# dmf.net
KiCad netlist of a schematic drawn in EAGLE
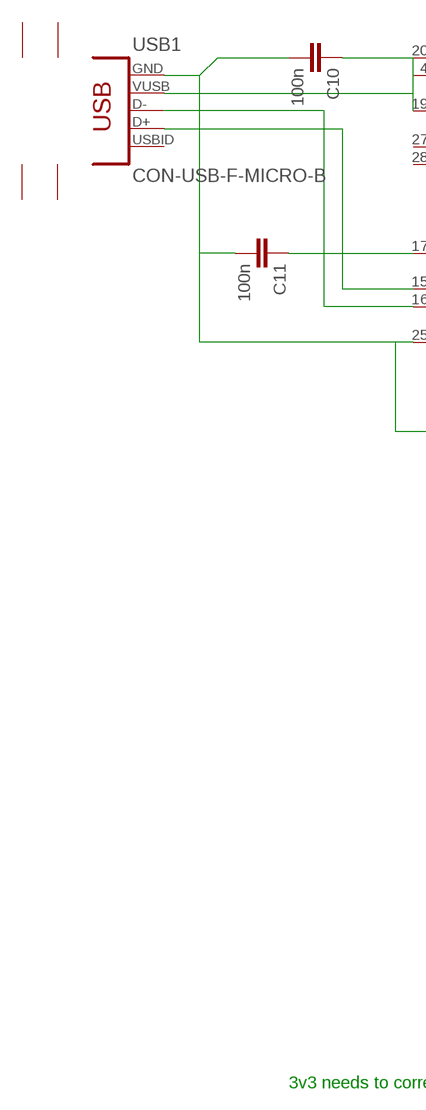
[diagram p0: schematic, sheet 1, part 1 of 2]
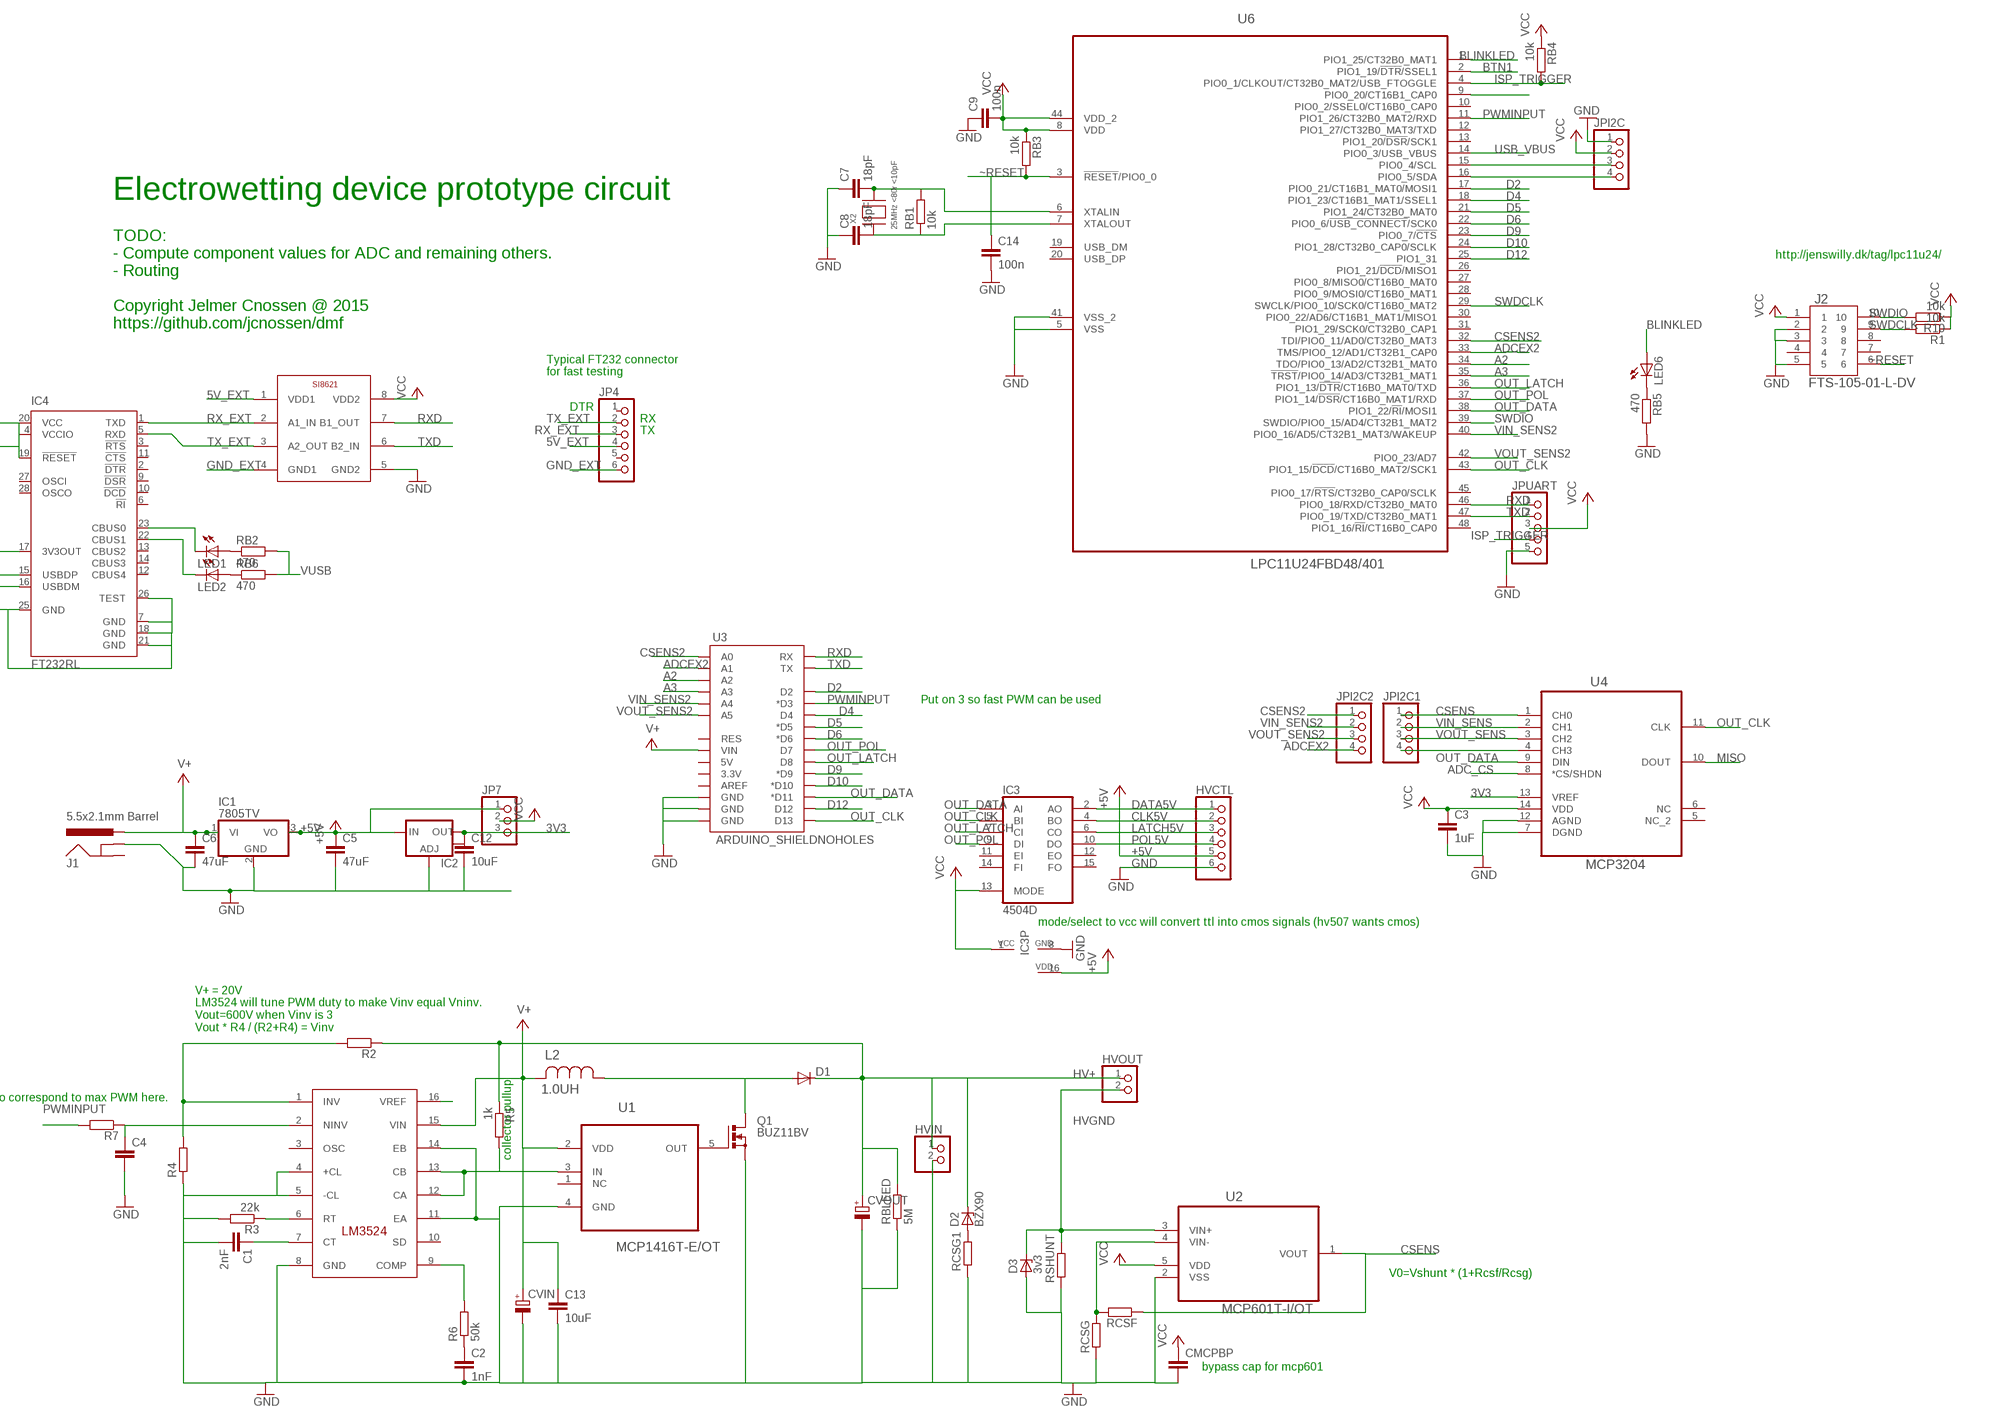
[diagram p1: schematic, sheet 1, part 2 of 2]

(export (version "E")
  (design (tool "Eeschema 10.0.6"))
  (components
    (comp (ref "C1")
      (value "2nF")
      (footprint "eagle-import:C0805")
      (libsource (lib "eagle-import") (part "C-EUC0805"))
    )
    (comp (ref "C2")
      (value "1nF")
      (footprint "eagle-import:C0805")
      (libsource (lib "eagle-import") (part "C-EUC0805"))
    )
    (comp (ref "C3")
      (value "1uF")
      (footprint "eagle-import:C0805")
      (libsource (lib "eagle-import") (part "C-EUC0805"))
    )
    (comp (ref "C4")
      (value "C-EUC0805")
      (footprint "eagle-import:C0805")
      (libsource (lib "eagle-import") (part "C-EUC0805"))
    )
    (comp (ref "C5")
      (value "47uF")
      (footprint "eagle-import:C1206")
      (libsource (lib "eagle-import") (part "C-EUC1206"))
    )
    (comp (ref "C6")
      (value "47uF")
      (footprint "eagle-import:C1206")
      (libsource (lib "eagle-import") (part "C-EUC1206"))
    )
    (comp (ref "C7")
      (value "18pF")
      (footprint "eagle-import:C0805")
      (libsource (lib "eagle-import") (part "C-EUC0805"))
    )
    (comp (ref "C8")
      (value "18pF")
      (footprint "eagle-import:C0805")
      (libsource (lib "eagle-import") (part "C-EUC0805"))
    )
    (comp (ref "C9")
      (value "100n")
      (footprint "eagle-import:C0805")
      (libsource (lib "eagle-import") (part "C-EUC0805"))
    )
    (comp (ref "C10")
      (value "100n")
      (footprint "eagle-import:C0805")
      (libsource (lib "eagle-import") (part "C-EUC0805"))
    )
    (comp (ref "C11")
      (value "100n")
      (footprint "eagle-import:C0805")
      (libsource (lib "eagle-import") (part "C-EUC0805"))
    )
    (comp (ref "C12")
      (value "10uF")
      (footprint "eagle-import:C1206")
      (libsource (lib "eagle-import") (part "C-EUC1206"))
    )
    (comp (ref "C13")
      (value "10uF")
      (footprint "eagle-import:C0805")
      (libsource (lib "eagle-import") (part "C-EUC0805"))
    )
    (comp (ref "C14")
      (value "100n")
      (footprint "eagle-import:C0805")
      (libsource (lib "eagle-import") (part "C-EUC0805"))
    )
    (comp (ref "CMCPBP")
      (value "C-EUC0805")
      (footprint "eagle-import:C0805")
      (libsource (lib "eagle-import") (part "C-EUC0805"))
    )
    (comp (ref "CVIN")
      (value "CPOL-EUE7.5-18")
      (footprint "eagle-import:E7,5-18")
      (libsource (lib "eagle-import") (part "CPOL-EUE7.5-18"))
    )
    (comp (ref "CVOUT")
      (value "CPOL-EUE7.5-18")
      (footprint "eagle-import:E7,5-18")
      (libsource (lib "eagle-import") (part "CPOL-EUE7.5-18"))
    )
    (comp (ref "D1")
      (value "DIODE-SMB")
      (footprint "eagle-import:SMB")
      (libsource (lib "eagle-import") (part "DIODE-SMB"))
    )
    (comp (ref "D2")
      (value "BZX90")
      (footprint "eagle-import:DO34Z7")
      (libsource (lib "eagle-import") (part "BZX90"))
    )
    (comp (ref "D3")
      (value "3v3")
      (footprint "eagle-import:SMB")
      (libsource (lib "eagle-import") (part "ZENER-DIODESMB"))
    )
    (comp (ref "HVCTL")
      (value "PINHD-1X06_2.54-S")
      (footprint "eagle-import:1X06-S")
      (libsource (lib "eagle-import") (part "PINHD-1X06_2.54-S"))
    )
    (comp (ref "HVIN")
      (value "PINHD-1X02_2.54")
      (footprint "eagle-import:1X02")
      (libsource (lib "eagle-import") (part "PINHD-1X02_2.54"))
    )
    (comp (ref "HVOUT")
      (value "PINHD-1X02_2.54")
      (footprint "eagle-import:1X02")
      (libsource (lib "eagle-import") (part "PINHD-1X02_2.54"))
    )
    (comp (ref "IC1")
      (value "7805TV")
      (footprint "eagle-import:TO220V")
      (libsource (lib "eagle-import") (part "78TV05"))
    )
    (comp (ref "IC2")
      (value "V_REG_LM1117SOT223")
      (footprint "eagle-import:SOT223")
      (libsource (lib "eagle-import") (part "V_REG_LM1117SOT223"))
    )
    (comp (ref "IC3")
      (value "4504D")
      (footprint "eagle-import:SO16")
      (libsource (lib "eagle-import") (part "4504D"))
    )
    (comp (ref "IC4")
      (value "FT232RL")
      (footprint "eagle-import:SSOP28")
      (libsource (lib "eagle-import") (part "FT232RL"))
    )
    (comp (ref "J1")
      (value "5.5x2.1mm Barrel")
      (footprint "eagle-import:POWER_JACK_SMD")
      (libsource (lib "eagle-import") (part "POWER_JACKSMD"))
    )
    (comp (ref "J2")
      (value "FTS-105-01-L-DV")
      (footprint "eagle-import:SAMTEC_FTS-105-01-L-DV")
      (libsource (lib "eagle-import") (part "FTS-105-01-L-DV"))
    )
    (comp (ref "JP4")
      (value "PINHD-1X06_2.54-S")
      (footprint "eagle-import:1X06-S")
      (libsource (lib "eagle-import") (part "PINHD-1X06_2.54-S"))
    )
    (comp (ref "JP7")
      (value "PINHD-1X03_2.54-S")
      (footprint "eagle-import:1X03-S")
      (libsource (lib "eagle-import") (part "PINHD-1X03_2.54-S"))
    )
    (comp (ref "JPI2C")
      (value "PINHD-1X04_2.54-S")
      (footprint "eagle-import:1X04-S")
      (libsource (lib "eagle-import") (part "PINHD-1X04_2.54-S"))
    )
    (comp (ref "JPI2C1")
      (value "PINHD-1X04_2.54-S")
      (footprint "eagle-import:1X04-S")
      (libsource (lib "eagle-import") (part "PINHD-1X04_2.54-S"))
    )
    (comp (ref "JPI2C2")
      (value "PINHD-1X04_2.54-S")
      (footprint "eagle-import:1X04-S")
      (libsource (lib "eagle-import") (part "PINHD-1X04_2.54-S"))
    )
    (comp (ref "JPUART")
      (value "PINHD-1X05_2.54-S")
      (footprint "eagle-import:1X05-S")
      (libsource (lib "eagle-import") (part "PINHD-1X05_2.54-S"))
    )
    (comp (ref "L2")
      (value "1.0UH")
      (footprint "eagle-import:IND_ELL6XH")
      (fields (field (name "MPN") "ELL6RH1R0M"))
      (libsource (lib "eagle-import") (part "ELL-6XH6RH1R0M"))
    )
    (comp (ref "LED1")
      (value "LEDCHIP-LED0805")
      (footprint "eagle-import:CHIP-LED0805")
      (libsource (lib "eagle-import") (part "LEDCHIP-LED0805"))
    )
    (comp (ref "LED2")
      (value "LEDCHIP-LED0805")
      (footprint "eagle-import:CHIP-LED0805")
      (libsource (lib "eagle-import") (part "LEDCHIP-LED0805"))
    )
    (comp (ref "LED6")
      (value "LEDCHIP-LED0805")
      (footprint "eagle-import:CHIP-LED0805")
      (libsource (lib "eagle-import") (part "LEDCHIP-LED0805"))
    )
    (comp (ref "Q1")
      (value "BUZ11BV")
      (footprint "eagle-import:TO220BV")
      (libsource (lib "eagle-import") (part "BUZ11BV"))
    )
    (comp (ref "R1")
      (value "10k")
      (footprint "eagle-import:R0603")
      (libsource (lib "eagle-import") (part "resistor_R-EU_R0603"))
    )
    (comp (ref "R2")
      (value "R-EU_R0603")
      (footprint "eagle-import:R0603")
      (libsource (lib "eagle-import") (part "R-EU_R0603"))
    )
    (comp (ref "R3")
      (value "22k")
      (footprint "eagle-import:R0603")
      (libsource (lib "eagle-import") (part "R-EU_R0603"))
    )
    (comp (ref "R4")
      (value "R-EU_R0603")
      (footprint "eagle-import:R0603")
      (libsource (lib "eagle-import") (part "R-EU_R0603"))
    )
    (comp (ref "R5")
      (value "1k")
      (footprint "eagle-import:R0603")
      (libsource (lib "eagle-import") (part "R-EU_R0603"))
    )
    (comp (ref "R6")
      (value "50k")
      (footprint "eagle-import:R0603")
      (libsource (lib "eagle-import") (part "R-EU_R0603"))
    )
    (comp (ref "R7")
      (value "R-EU_R0603")
      (footprint "eagle-import:R0603")
      (libsource (lib "eagle-import") (part "R-EU_R0603"))
    )
    (comp (ref "R10")
      (value "10k")
      (footprint "eagle-import:R0603")
      (libsource (lib "eagle-import") (part "resistor_R-EU_R0603"))
    )
    (comp (ref "RB1")
      (value "10k")
      (footprint "eagle-import:R0603")
      (libsource (lib "eagle-import") (part "R-EU_R0603"))
    )
    (comp (ref "RB2")
      (value "470")
      (footprint "eagle-import:R0603")
      (libsource (lib "eagle-import") (part "R-EU_R0603"))
    )
    (comp (ref "RB3")
      (value "10k")
      (footprint "eagle-import:R0603")
      (libsource (lib "eagle-import") (part "R-EU_R0603"))
    )
    (comp (ref "RB4")
      (value "10k")
      (footprint "eagle-import:R0603")
      (libsource (lib "eagle-import") (part "R-EU_R0603"))
    )
    (comp (ref "RB5")
      (value "470")
      (footprint "eagle-import:R0402")
      (libsource (lib "eagle-import") (part "R-EU_R0402"))
    )
    (comp (ref "RB6")
      (value "470")
      (footprint "eagle-import:R0603")
      (libsource (lib "eagle-import") (part "R-EU_R0603"))
    )
    (comp (ref "RBLEED")
      (value "5M")
      (footprint "eagle-import:R1206")
      (libsource (lib "eagle-import") (part "R-EU_R1206"))
    )
    (comp (ref "RCSF")
      (value "R-EU_R0603")
      (footprint "eagle-import:R0603")
      (libsource (lib "eagle-import") (part "R-EU_R0603"))
    )
    (comp (ref "RCSG")
      (value "R-EU_R0603")
      (footprint "eagle-import:R0603")
      (libsource (lib "eagle-import") (part "R-EU_R0603"))
    )
    (comp (ref "RCSG1")
      (value "R-EU_R1206")
      (footprint "eagle-import:R1206")
      (libsource (lib "eagle-import") (part "R-EU_R1206"))
    )
    (comp (ref "RSHUNT")
      (value "R-EU_R1206")
      (footprint "eagle-import:R1206")
      (libsource (lib "eagle-import") (part "R-EU_R1206"))
    )
    (comp (ref "U$1")
      (value "LM3524")
      (footprint "eagle-import:SO16")
      (libsource (lib "eagle-import") (part "LM3524"))
    )
    (comp (ref "U$2")
      (value "SI8621AB")
      (footprint "eagle-import:SO8")
      (libsource (lib "eagle-import") (part "SI8621AB"))
    )
    (comp (ref "U1")
      (value "MCP1416T-E/OT")
      (footprint "eagle-import:SOT95P270X145-5N")
      (libsource (lib "eagle-import") (part "MCP1416T-E/OT"))
    )
    (comp (ref "U2")
      (value "MCP601T-I/OT")
      (footprint "eagle-import:SOT95P320X145-5N")
      (libsource (lib "eagle-import") (part "MCP601T-I/OT"))
    )
    (comp (ref "U3")
      (value "ARDUINO_SHIELDNOHOLES")
      (footprint "eagle-import:DUEMILANOVE_SHIELD_NOHOLES")
      (libsource (lib "eagle-import") (part "ARDUINO_SHIELDNOHOLES"))
    )
    (comp (ref "U4")
      (value "MCP3204")
      (footprint "eagle-import:SOIC127P600X175-14N")
      (fields (field (name "MPN") "MCP3204-CI/SL"))
      (libsource (lib "eagle-import") (part "MCP3204-CI/SL"))
    )
    (comp (ref "U6")
      (value "LPC11U24FBD48/401")
      (footprint "eagle-import:QFP50P900X900X160-48N")
      (libsource (lib "eagle-import") (part "LPC11U24FBD48/401"))
    )
    (comp (ref "USB1")
      (value "CON-USB-F-MICRO-B")
      (footprint "eagle-import:CONN_USB_MICRO-B")
      (libsource (lib "eagle-import") (part "CON-USB-F-MICRO-B"))
    )
    (comp (ref "X2")
      (value "25MHz <80r <10pF")
      (footprint "eagle-import:NX5032")
      (libsource (lib "eagle-import") (part "XTALNX5032"))
    )
  )
  (nets
    (net (code "1") (name "+5V") (class "Default")
      (node (ref "C5") (pin "1") (pinfunction "1_1") (pintype "passive"))
      (node (ref "HVCTL") (pin "5") (pinfunction "5_5") (pintype "passive"))
      (node (ref "IC1") (pin "3") (pinfunction "VO_3") (pintype "passive"))
      (node (ref "IC2") (pin "3") (pinfunction "IN_3") (pintype "input"))
      (node (ref "IC3") (pin "16") (pinfunction "VDD_16") (pintype "power_in"))
      (node (ref "JP7") (pin "1") (pinfunction "1_1") (pintype "passive"))
    )
    (net (code "2") (name "3V3") (class "Default")
      (node (ref "C12") (pin "1") (pinfunction "1_1") (pintype "passive"))
      (node (ref "IC2") (pin "2") (pinfunction "OUT_2") (pintype "output"))
      (node (ref "JP7") (pin "3") (pinfunction "3_3") (pintype "passive"))
      (node (ref "U4") (pin "13") (pinfunction "VREF_13") (pintype "input"))
    )
    (net (code "3") (name "5V_EXT") (class "Default")
      (node (ref "JP4") (pin "4") (pinfunction "4_4") (pintype "passive"))
      (node (ref "U$2") (pin "1") (pinfunction "VDD1_1") (pintype "bidirectional"))
    )
    (net (code "4") (name "A2") (class "Default")
      (node (ref "U3") (pin "A2") (pinfunction "A2_A2") (pintype "bidirectional"))
      (node (ref "U6") (pin "34") (pinfunction "TDO/PIO0_13/AD2/CT32B1_MAT0_34") (pintype "passive"))
    )
    (net (code "5") (name "A3") (class "Default")
      (node (ref "U3") (pin "A3") (pinfunction "A3_A3") (pintype "bidirectional"))
      (node (ref "U6") (pin "35") (pinfunction "~{TRST}/PIO0_14/AD3/CT32B1_MAT1_35") (pintype "passive"))
    )
    (net (code "6") (name "ADCEX2") (class "Default")
      (node (ref "JPI2C2") (pin "4") (pinfunction "4_4") (pintype "passive"))
      (node (ref "U3") (pin "A1") (pinfunction "A1_A1") (pintype "bidirectional"))
      (node (ref "U6") (pin "33") (pinfunction "TMS/PIO0_12/AD1/CT32B1_CAP0_33") (pintype "passive"))
    )
    (net (code "7") (name "ADC_CS") (class "Default")
      (node (ref "U4") (pin "8") (pinfunction "*CS/SHDN_8") (pintype "input"))
    )
    (net (code "8") (name "BLINKLED") (class "Default")
      (node (ref "LED6") (pin "A") (pinfunction "A_A") (pintype "passive"))
      (node (ref "U6") (pin "1") (pinfunction "PIO1_25/CT32B0_MAT1_1") (pintype "bidirectional"))
    )
    (net (code "9") (name "BTN1") (class "Default")
      (node (ref "U6") (pin "2") (pinfunction "PIO1_19/~{DTR}/SSEL1_2") (pintype "bidirectional"))
    )
    (net (code "10") (name "CLK5V") (class "Default")
      (node (ref "HVCTL") (pin "2") (pinfunction "2_2") (pintype "passive"))
      (node (ref "IC3") (pin "4") (pinfunction "BO_4") (pintype "output"))
    )
    (net (code "11") (name "CSENS") (class "Default")
      (node (ref "JPI2C1") (pin "1") (pinfunction "1_1") (pintype "passive"))
      (node (ref "RCSF") (pin "1") (pinfunction "1_1") (pintype "passive"))
      (node (ref "U2") (pin "1") (pinfunction "VOUT_1") (pintype "output"))
      (node (ref "U4") (pin "1") (pinfunction "CH0_1") (pintype "input"))
    )
    (net (code "12") (name "CSENS2") (class "Default")
      (node (ref "JPI2C2") (pin "1") (pinfunction "1_1") (pintype "passive"))
      (node (ref "U3") (pin "A0") (pinfunction "A0_A0") (pintype "bidirectional"))
      (node (ref "U6") (pin "32") (pinfunction "TDI/PIO0_11/AD0/CT32B0_MAT3_32") (pintype "passive"))
    )
    (net (code "13") (name "D2") (class "Default")
      (node (ref "U3") (pin "D2") (pinfunction "D2_D2") (pintype "bidirectional"))
      (node (ref "U6") (pin "17") (pinfunction "PIO0_21/CT16B1_MAT0/MOSI1_17") (pintype "bidirectional"))
    )
    (net (code "14") (name "D4") (class "Default")
      (node (ref "U3") (pin "D4") (pinfunction "D4_D4") (pintype "bidirectional"))
      (node (ref "U6") (pin "18") (pinfunction "PIO1_23/CT16B1_MAT1/SSEL1_18") (pintype "bidirectional"))
    )
    (net (code "15") (name "D5") (class "Default")
      (node (ref "U3") (pin "D5") (pinfunction "*D5_D5") (pintype "bidirectional"))
      (node (ref "U6") (pin "21") (pinfunction "PIO1_24/CT32B0_MAT0_21") (pintype "bidirectional"))
    )
    (net (code "16") (name "D6") (class "Default")
      (node (ref "U3") (pin "D6") (pinfunction "*D6_D6") (pintype "bidirectional"))
      (node (ref "U6") (pin "22") (pinfunction "PIO0_6/~{USB_CONNECT}/SCK0_22") (pintype "bidirectional"))
    )
    (net (code "17") (name "D9") (class "Default")
      (node (ref "U3") (pin "D9") (pinfunction "*D9_D9") (pintype "bidirectional"))
      (node (ref "U6") (pin "23") (pinfunction "PIO0_7/~{CTS}_23") (pintype "bidirectional"))
    )
    (net (code "18") (name "D10") (class "Default")
      (node (ref "U3") (pin "D10") (pinfunction "*D10_D10") (pintype "bidirectional"))
      (node (ref "U6") (pin "24") (pinfunction "PIO1_28/CT32B0_CAP0/SCLK_24") (pintype "bidirectional"))
    )
    (net (code "19") (name "D12") (class "Default")
      (node (ref "U3") (pin "D12") (pinfunction "D12_D12") (pintype "bidirectional"))
      (node (ref "U6") (pin "25") (pinfunction "PIO1_31_25") (pintype "bidirectional"))
    )
    (net (code "20") (name "DATA5V") (class "Default")
      (node (ref "HVCTL") (pin "1") (pinfunction "1_1") (pintype "passive"))
      (node (ref "IC3") (pin "2") (pinfunction "AO_2") (pintype "output"))
    )
    (net (code "21") (name "GND") (class "Default")
      (node (ref "C1") (pin "2") (pinfunction "2_2") (pintype "passive"))
      (node (ref "C12") (pin "2") (pinfunction "2_2") (pintype "passive"))
      (node (ref "C13") (pin "2") (pinfunction "2_2") (pintype "passive"))
      (node (ref "C14") (pin "2") (pinfunction "2_2") (pintype "passive"))
      (node (ref "C2") (pin "2") (pinfunction "2_2") (pintype "passive"))
      (node (ref "C3") (pin "2") (pinfunction "2_2") (pintype "passive"))
      (node (ref "C4") (pin "2") (pinfunction "2_2") (pintype "passive"))
      (node (ref "C5") (pin "2") (pinfunction "2_2") (pintype "passive"))
      (node (ref "C6") (pin "2") (pinfunction "2_2") (pintype "passive"))
      (node (ref "C7") (pin "1") (pinfunction "1_1") (pintype "passive"))
      (node (ref "C8") (pin "1") (pinfunction "1_1") (pintype "passive"))
      (node (ref "C9") (pin "1") (pinfunction "1_1") (pintype "passive"))
      (node (ref "CMCPBP") (pin "2") (pinfunction "2_2") (pintype "passive"))
      (node (ref "CVIN") (pin "-") (pinfunction "-_-") (pintype "passive"))
      (node (ref "CVOUT") (pin "-") (pinfunction "-_-") (pintype "passive"))
      (node (ref "D3") (pin "A") (pinfunction "A_A") (pintype "passive"))
      (node (ref "HVCTL") (pin "6") (pinfunction "6_6") (pintype "passive"))
      (node (ref "HVIN") (pin "2") (pinfunction "2_2") (pintype "passive"))
      (node (ref "IC1") (pin "2") (pinfunction "GND_2") (pintype "passive"))
      (node (ref "IC2") (pin "1") (pinfunction "ADJ_1") (pintype "input"))
      (node (ref "IC3") (pin "8") (pinfunction "GND_8") (pintype "power_in"))
      (node (ref "J1") (pin "GND") (pinfunction "GNDBREAK_GND") (pintype "bidirectional"))
      (node (ref "J2") (pin "2") (pinfunction "2_2") (pintype "passive"))
      (node (ref "J2") (pin "3") (pinfunction "3_3") (pintype "passive"))
      (node (ref "J2") (pin "5") (pinfunction "5_5") (pintype "passive"))
      (node (ref "JPI2C") (pin "1") (pinfunction "1_1") (pintype "passive"))
      (node (ref "JPUART") (pin "5") (pinfunction "5_5") (pintype "passive"))
      (node (ref "Q1") (pin "S") (pinfunction "S_S") (pintype "passive"))
      (node (ref "R3") (pin "2") (pinfunction "2_2") (pintype "passive"))
      (node (ref "R4") (pin "1") (pinfunction "1_1") (pintype "passive"))
      (node (ref "RB5") (pin "2") (pinfunction "2_2") (pintype "passive"))
      (node (ref "RBLEED") (pin "1") (pinfunction "1_1") (pintype "passive"))
      (node (ref "RCSG") (pin "1") (pinfunction "1_1") (pintype "passive"))
      (node (ref "RCSG1") (pin "1") (pinfunction "1_1") (pintype "passive"))
      (node (ref "RSHUNT") (pin "1") (pinfunction "1_1") (pintype "passive"))
      (node (ref "U$1") (pin "11") (pinfunction "EA_11") (pintype "output"))
      (node (ref "U$1") (pin "14") (pinfunction "EB_14") (pintype "output"))
      (node (ref "U$1") (pin "4") (pinfunction "+CL_4") (pintype "output"))
      (node (ref "U$1") (pin "5") (pinfunction "-CL_5") (pintype "output"))
      (node (ref "U$1") (pin "8") (pinfunction "GND_8") (pintype "output"))
      (node (ref "U$2") (pin "5") (pinfunction "GND2_5") (pintype "bidirectional"))
      (node (ref "U1") (pin "4") (pinfunction "GND_4") (pintype "passive"))
      (node (ref "U2") (pin "2") (pinfunction "VSS_2") (pintype "passive"))
      (node (ref "U3") (pin "GND@0") (pinfunction "GND_GND@0") (pintype "bidirectional"))
      (node (ref "U3") (pin "GND@1") (pinfunction "GND_GND@1") (pintype "bidirectional"))
      (node (ref "U3") (pin "GND@2") (pinfunction "GND_GND@2") (pintype "bidirectional"))
      (node (ref "U4") (pin "12") (pinfunction "AGND_12") (pintype "passive"))
      (node (ref "U4") (pin "7") (pinfunction "DGND_7") (pintype "passive"))
      (node (ref "U6") (pin "41") (pinfunction "VSS_2_41") (pintype "passive"))
      (node (ref "U6") (pin "5") (pinfunction "VSS_5") (pintype "passive"))
    )
    (net (code "22") (name "GND_EXT") (class "Default")
      (node (ref "C10") (pin "2") (pinfunction "2_2") (pintype "passive"))
      (node (ref "C11") (pin "2") (pinfunction "2_2") (pintype "passive"))
      (node (ref "IC4") (pin "18") (pinfunction "GND_18") (pintype "power_in"))
      (node (ref "IC4") (pin "21") (pinfunction "GND_21") (pintype "power_in"))
      (node (ref "IC4") (pin "25") (pinfunction "GND_25") (pintype "power_in"))
      (node (ref "IC4") (pin "26") (pinfunction "TEST_26") (pintype "input"))
      (node (ref "IC4") (pin "7") (pinfunction "GND_7") (pintype "power_in"))
      (node (ref "JP4") (pin "6") (pinfunction "6_6") (pintype "passive"))
      (node (ref "U$2") (pin "4") (pinfunction "GND1_4") (pintype "bidirectional"))
      (node (ref "USB1") (pin "P5") (pinfunction "GND_P5") (pintype "bidirectional"))
    )
    (net (code "23") (name "HV+") (class "Default")
      (node (ref "CVOUT") (pin "+") (pinfunction "+_+") (pintype "passive"))
      (node (ref "D1") (pin "C") (pinfunction "C_C") (pintype "passive"))
      (node (ref "D2") (pin "C") (pinfunction "C_C") (pintype "passive"))
      (node (ref "HVIN") (pin "1") (pinfunction "1_1") (pintype "passive"))
      (node (ref "HVOUT") (pin "1") (pinfunction "1_1") (pintype "passive"))
      (node (ref "R2") (pin "1") (pinfunction "1_1") (pintype "passive"))
      (node (ref "R5") (pin "1") (pinfunction "1_1") (pintype "passive"))
      (node (ref "RBLEED") (pin "2") (pinfunction "2_2") (pintype "passive"))
    )
    (net (code "24") (name "HVGND") (class "Default")
      (node (ref "D3") (pin "C") (pinfunction "C_C") (pintype "passive"))
      (node (ref "HVOUT") (pin "2") (pinfunction "2_2") (pintype "passive"))
      (node (ref "RSHUNT") (pin "2") (pinfunction "2_2") (pintype "passive"))
      (node (ref "U2") (pin "3") (pinfunction "VIN+_3") (pintype "input"))
    )
    (net (code "25") (name "ISP_TRIGGER") (class "Default")
      (node (ref "JPUART") (pin "4") (pinfunction "4_4") (pintype "passive"))
      (node (ref "RB4") (pin "2") (pinfunction "2_2") (pintype "passive"))
      (node (ref "U6") (pin "4") (pinfunction "PIO0_1/CLKOUT/CT32B0_MAT2/USB_FTOGGLE_4") (pintype "bidirectional"))
    )
    (net (code "26") (name "LATCH5V") (class "Default")
      (node (ref "HVCTL") (pin "3") (pinfunction "3_3") (pintype "passive"))
      (node (ref "IC3") (pin "6") (pinfunction "CO_6") (pintype "output"))
    )
    (net (code "27") (name "MISO") (class "Default")
      (node (ref "U4") (pin "10") (pinfunction "DOUT_10") (pintype "output"))
    )
    (net (code "28") (name "Net-(C2-Pad1)") (class "Default")
      (node (ref "C2") (pin "1") (pinfunction "1_1") (pintype "passive"))
      (node (ref "R6") (pin "1") (pinfunction "1_1") (pintype "passive"))
    )
    (net (code "29") (name "Net-(D1-PadA)") (class "Default")
      (node (ref "D1") (pin "A") (pinfunction "A_A") (pintype "passive"))
      (node (ref "L2") (pin "1") (pinfunction "1_1") (pintype "passive"))
      (node (ref "Q1") (pin "D") (pinfunction "D_D") (pintype "passive"))
    )
    (net (code "30") (name "Net-(D2-PadA)") (class "Default")
      (node (ref "D2") (pin "A") (pinfunction "A_A") (pintype "passive"))
      (node (ref "RCSG1") (pin "2") (pinfunction "2_2") (pintype "passive"))
    )
    (net (code "31") (name "Net-(IC4-3V3OUT)") (class "Default")
      (node (ref "C11") (pin "1") (pinfunction "1_1") (pintype "passive"))
      (node (ref "IC4") (pin "17") (pinfunction "3V3OUT_17") (pintype "output"))
    )
    (net (code "32") (name "Net-(IC4-CBUS0)") (class "Default")
      (node (ref "IC4") (pin "23") (pinfunction "CBUS0_23") (pintype "bidirectional"))
      (node (ref "LED1") (pin "C") (pinfunction "C_C") (pintype "passive"))
    )
    (net (code "33") (name "Net-(IC4-CBUS1)") (class "Default")
      (node (ref "IC4") (pin "22") (pinfunction "CBUS1_22") (pintype "bidirectional"))
      (node (ref "LED2") (pin "C") (pinfunction "C_C") (pintype "passive"))
    )
    (net (code "34") (name "Net-(IC4-USBDM)") (class "Default")
      (node (ref "IC4") (pin "16") (pinfunction "USBDM_16") (pintype "bidirectional"))
      (node (ref "USB1") (pin "P2") (pinfunction "D-_P2") (pintype "bidirectional"))
    )
    (net (code "35") (name "Net-(IC4-USBDP)") (class "Default")
      (node (ref "IC4") (pin "15") (pinfunction "USBDP_15") (pintype "bidirectional"))
      (node (ref "USB1") (pin "P3") (pinfunction "D+_P3") (pintype "bidirectional"))
    )
    (net (code "36") (name "Net-(LED1-PadA)") (class "Default")
      (node (ref "LED1") (pin "A") (pinfunction "A_A") (pintype "passive"))
      (node (ref "RB2") (pin "1") (pinfunction "1_1") (pintype "passive"))
    )
    (net (code "37") (name "Net-(LED2-PadA)") (class "Default")
      (node (ref "LED2") (pin "A") (pinfunction "A_A") (pintype "passive"))
      (node (ref "RB6") (pin "1") (pinfunction "1_1") (pintype "passive"))
    )
    (net (code "38") (name "Net-(LED6-PadC)") (class "Default")
      (node (ref "LED6") (pin "C") (pinfunction "C_C") (pintype "passive"))
      (node (ref "RB5") (pin "1") (pinfunction "1_1") (pintype "passive"))
    )
    (net (code "39") (name "Net-(U$1-CA)") (class "Default")
      (node (ref "R5") (pin "2") (pinfunction "2_2") (pintype "passive"))
      (node (ref "U$1") (pin "12") (pinfunction "CA_12") (pintype "output"))
      (node (ref "U$1") (pin "13") (pinfunction "CB_13") (pintype "output"))
      (node (ref "U1") (pin "3") (pinfunction "IN_3") (pintype "input"))
    )
    (net (code "40") (name "Net-(U$1-COMP)") (class "Default")
      (node (ref "R6") (pin "2") (pinfunction "2_2") (pintype "passive"))
      (node (ref "U$1") (pin "9") (pinfunction "COMP_9") (pintype "output"))
    )
    (net (code "41") (name "Net-(U$1-CT)") (class "Default")
      (node (ref "C1") (pin "1") (pinfunction "1_1") (pintype "passive"))
      (node (ref "U$1") (pin "7") (pinfunction "CT_7") (pintype "output"))
    )
    (net (code "42") (name "Net-(U$1-INV)") (class "Default")
      (node (ref "R2") (pin "2") (pinfunction "2_2") (pintype "passive"))
      (node (ref "R4") (pin "2") (pinfunction "2_2") (pintype "passive"))
      (node (ref "U$1") (pin "1") (pinfunction "INV_1") (pintype "output"))
    )
    (net (code "43") (name "Net-(U$1-NINV)") (class "Default")
      (node (ref "C4") (pin "1") (pinfunction "1_1") (pintype "passive"))
      (node (ref "R7") (pin "1") (pinfunction "1_1") (pintype "passive"))
      (node (ref "U$1") (pin "2") (pinfunction "NINV_2") (pintype "output"))
    )
    (net (code "44") (name "Net-(U$1-RT)") (class "Default")
      (node (ref "R3") (pin "1") (pinfunction "1_1") (pintype "passive"))
      (node (ref "U$1") (pin "6") (pinfunction "RT_6") (pintype "output"))
    )
    (net (code "45") (name "Net-(U1-OUT)") (class "Default")
      (node (ref "Q1") (pin "G") (pinfunction "G_G") (pintype "passive"))
      (node (ref "U1") (pin "5") (pinfunction "OUT_5") (pintype "output"))
    )
    (net (code "46") (name "Net-(U2-VIN-)") (class "Default")
      (node (ref "RCSF") (pin "2") (pinfunction "2_2") (pintype "passive"))
      (node (ref "RCSG") (pin "2") (pinfunction "2_2") (pintype "passive"))
      (node (ref "U2") (pin "4") (pinfunction "VIN-_4") (pintype "input"))
    )
    (net (code "47") (name "Net-(U4-CH3)") (class "Default")
      (node (ref "JPI2C1") (pin "4") (pinfunction "4_4") (pintype "passive"))
      (node (ref "U4") (pin "4") (pinfunction "CH3_4") (pintype "input"))
    )
    (net (code "48") (name "Net-(U6-PIO0_4{slash}SCL)") (class "Default")
      (node (ref "JPI2C") (pin "3") (pinfunction "3_3") (pintype "passive"))
      (node (ref "U6") (pin "15") (pinfunction "PIO0_4/SCL_15") (pintype "bidirectional"))
    )
    (net (code "49") (name "Net-(U6-PIO0_5{slash}SDA)") (class "Default")
      (node (ref "JPI2C") (pin "4") (pinfunction "4_4") (pintype "passive"))
      (node (ref "U6") (pin "16") (pinfunction "PIO0_5/SDA_16") (pintype "bidirectional"))
    )
    (net (code "50") (name "Net-(U6-XTALIN)") (class "Default")
      (node (ref "C7") (pin "2") (pinfunction "2_2") (pintype "passive"))
      (node (ref "RB1") (pin "2") (pinfunction "2_2") (pintype "passive"))
      (node (ref "U6") (pin "6") (pinfunction "XTALIN_6") (pintype "passive"))
      (node (ref "X2") (pin "P$2") (pinfunction "P$2_P$2") (pintype "bidirectional"))
    )
    (net (code "51") (name "Net-(U6-XTALOUT)") (class "Default")
      (node (ref "C8") (pin "2") (pinfunction "2_2") (pintype "passive"))
      (node (ref "RB1") (pin "1") (pinfunction "1_1") (pintype "passive"))
      (node (ref "U6") (pin "7") (pinfunction "XTALOUT_7") (pintype "passive"))
      (node (ref "X2") (pin "P$1") (pinfunction "P$1_P$1") (pintype "bidirectional"))
    )
    (net (code "52") (name "OUT_CLK") (class "Default")
      (node (ref "IC3") (pin "5") (pinfunction "BI_5") (pintype "input"))
      (node (ref "U3") (pin "D13") (pinfunction "D13_D13") (pintype "bidirectional"))
      (node (ref "U4") (pin "11") (pinfunction "CLK_11") (pintype "input"))
      (node (ref "U6") (pin "43") (pinfunction "PIO1_15/~{DCD}/CT16B0_MAT2/SCK1_43") (pintype "bidirectional"))
    )
    (net (code "53") (name "OUT_DATA") (class "Default")
      (node (ref "IC3") (pin "3") (pinfunction "AI_3") (pintype "input"))
      (node (ref "U3") (pin "D11") (pinfunction "*D11_D11") (pintype "bidirectional"))
      (node (ref "U4") (pin "9") (pinfunction "DIN_9") (pintype "input"))
      (node (ref "U6") (pin "38") (pinfunction "PIO1_22/~{RI}/MOSI1_38") (pintype "bidirectional"))
    )
    (net (code "54") (name "OUT_LATCH") (class "Default")
      (node (ref "IC3") (pin "7") (pinfunction "CI_7") (pintype "input"))
      (node (ref "U3") (pin "D8") (pinfunction "D8_D8") (pintype "bidirectional"))
      (node (ref "U6") (pin "36") (pinfunction "PIO1_13/~{DTR}/CT16B0_MAT0/TXD_36") (pintype "bidirectional"))
    )
    (net (code "55") (name "OUT_POL") (class "Default")
      (node (ref "IC3") (pin "9") (pinfunction "DI_9") (pintype "input"))
      (node (ref "U3") (pin "D7") (pinfunction "D7_D7") (pintype "bidirectional"))
      (node (ref "U6") (pin "37") (pinfunction "PIO1_14/~{DSR}/CT16B0_MAT1/RXD_37") (pintype "bidirectional"))
    )
    (net (code "56") (name "POL5V") (class "Default")
      (node (ref "HVCTL") (pin "4") (pinfunction "4_4") (pintype "passive"))
      (node (ref "IC3") (pin "10") (pinfunction "DO_10") (pintype "output"))
    )
    (net (code "57") (name "PWMINPUT") (class "Default")
      (node (ref "R7") (pin "2") (pinfunction "2_2") (pintype "passive"))
      (node (ref "U3") (pin "D3") (pinfunction "*D3_D3") (pintype "bidirectional"))
      (node (ref "U6") (pin "11") (pinfunction "PIO1_26/CT32B0_MAT2/RXD_11") (pintype "bidirectional"))
    )
    (net (code "58") (name "RXD") (class "Default")
      (node (ref "JPUART") (pin "1") (pinfunction "1_1") (pintype "passive"))
      (node (ref "U$2") (pin "7") (pinfunction "B1_OUT_7") (pintype "bidirectional"))
      (node (ref "U3") (pin "RX") (pinfunction "RX_RX") (pintype "bidirectional"))
      (node (ref "U6") (pin "46") (pinfunction "PIO0_18/RXD/CT32B0_MAT0_46") (pintype "bidirectional"))
    )
    (net (code "59") (name "RX_EXT") (class "Default")
      (node (ref "IC4") (pin "1") (pinfunction "TXD_1") (pintype "output"))
      (node (ref "JP4") (pin "3") (pinfunction "3_3") (pintype "passive"))
      (node (ref "U$2") (pin "2") (pinfunction "A1_IN_2") (pintype "bidirectional"))
    )
    (net (code "60") (name "SWDCLK") (class "Default")
      (node (ref "J2") (pin "9") (pinfunction "9_9") (pintype "passive"))
      (node (ref "R1") (pin "2") (pinfunction "2_2") (pintype "passive"))
      (node (ref "U6") (pin "29") (pinfunction "SWCLK/PIO0_10/SCK0/CT16B0_MAT2_29") (pintype "passive"))
    )
    (net (code "61") (name "SWDIO") (class "Default")
      (node (ref "J2") (pin "10") (pinfunction "10_10") (pintype "passive"))
      (node (ref "R10") (pin "2") (pinfunction "2_2") (pintype "passive"))
      (node (ref "U6") (pin "39") (pinfunction "SWDIO/PIO0_15/AD4/CT32B1_MAT2_39") (pintype "passive"))
    )
    (net (code "62") (name "TXD") (class "Default")
      (node (ref "JPUART") (pin "2") (pinfunction "2_2") (pintype "passive"))
      (node (ref "U$2") (pin "6") (pinfunction "B2_IN_6") (pintype "bidirectional"))
      (node (ref "U3") (pin "TX") (pinfunction "TX_TX") (pintype "bidirectional"))
      (node (ref "U6") (pin "47") (pinfunction "PIO0_19/TXD/CT32B0_MAT1_47") (pintype "bidirectional"))
    )
    (net (code "63") (name "TX_EXT") (class "Default")
      (node (ref "IC4") (pin "5") (pinfunction "RXD_5") (pintype "input"))
      (node (ref "JP4") (pin "2") (pinfunction "2_2") (pintype "passive"))
      (node (ref "U$2") (pin "3") (pinfunction "A2_OUT_3") (pintype "bidirectional"))
    )
    (net (code "64") (name "USB_VBUS") (class "Default")
      (node (ref "U6") (pin "14") (pinfunction "PIO0_3/USB_VBUS_14") (pintype "bidirectional"))
    )
    (net (code "65") (name "V+") (class "Default")
      (node (ref "C13") (pin "1") (pinfunction "1_1") (pintype "passive"))
      (node (ref "C6") (pin "1") (pinfunction "1_1") (pintype "passive"))
      (node (ref "CVIN") (pin "+") (pinfunction "+_+") (pintype "passive"))
      (node (ref "IC1") (pin "1") (pinfunction "VI_1") (pintype "input"))
      (node (ref "J1") (pin "VIN0") (pinfunction "PWR_VIN0") (pintype "bidirectional"))
      (node (ref "L2") (pin "2") (pinfunction "2_2") (pintype "passive"))
      (node (ref "U$1") (pin "15") (pinfunction "VIN_15") (pintype "output"))
      (node (ref "U1") (pin "2") (pinfunction "VDD_2") (pintype "power_in"))
      (node (ref "U3") (pin "VIN") (pinfunction "VIN_VIN") (pintype "bidirectional"))
    )
    (net (code "66") (name "VCC") (class "Default")
      (node (ref "C3") (pin "1") (pinfunction "1_1") (pintype "passive"))
      (node (ref "C9") (pin "2") (pinfunction "2_2") (pintype "passive"))
      (node (ref "CMCPBP") (pin "1") (pinfunction "1_1") (pintype "passive"))
      (node (ref "IC3") (pin "1") (pinfunction "VCC_1") (pintype "power_in"))
      (node (ref "IC3") (pin "13") (pinfunction "MODE_13") (pintype "input"))
      (node (ref "J2") (pin "1") (pinfunction "1_1") (pintype "passive"))
      (node (ref "JP7") (pin "2") (pinfunction "2_2") (pintype "passive"))
      (node (ref "JPI2C") (pin "2") (pinfunction "2_2") (pintype "passive"))
      (node (ref "JPUART") (pin "3") (pinfunction "3_3") (pintype "passive"))
      (node (ref "R1") (pin "1") (pinfunction "1_1") (pintype "passive"))
      (node (ref "R10") (pin "1") (pinfunction "1_1") (pintype "passive"))
      (node (ref "RB3") (pin "1") (pinfunction "1_1") (pintype "passive"))
      (node (ref "RB4") (pin "1") (pinfunction "1_1") (pintype "passive"))
      (node (ref "U$2") (pin "8") (pinfunction "VDD2_8") (pintype "bidirectional"))
      (node (ref "U2") (pin "5") (pinfunction "VDD_5") (pintype "power_in"))
      (node (ref "U4") (pin "14") (pinfunction "VDD_14") (pintype "power_in"))
      (node (ref "U6") (pin "44") (pinfunction "VDD_2_44") (pintype "power_in"))
      (node (ref "U6") (pin "8") (pinfunction "VDD_8") (pintype "power_in"))
    )
    (net (code "67") (name "VIN_SENS") (class "Default")
      (node (ref "JPI2C1") (pin "2") (pinfunction "2_2") (pintype "passive"))
      (node (ref "U4") (pin "2") (pinfunction "CH1_2") (pintype "input"))
    )
    (net (code "68") (name "VIN_SENS2") (class "Default")
      (node (ref "JPI2C2") (pin "2") (pinfunction "2_2") (pintype "passive"))
      (node (ref "U3") (pin "A4") (pinfunction "A4_A4") (pintype "bidirectional"))
      (node (ref "U6") (pin "40") (pinfunction "PIO0_16/AD5/CT32B1_MAT3/WAKEUP_40") (pintype "bidirectional"))
    )
    (net (code "69") (name "VOUT_SENS") (class "Default")
      (node (ref "JPI2C1") (pin "3") (pinfunction "3_3") (pintype "passive"))
      (node (ref "U4") (pin "3") (pinfunction "CH2_3") (pintype "input"))
    )
    (net (code "70") (name "VOUT_SENS2") (class "Default")
      (node (ref "JPI2C2") (pin "3") (pinfunction "3_3") (pintype "passive"))
      (node (ref "U3") (pin "A5") (pinfunction "A5_A5") (pintype "bidirectional"))
      (node (ref "U6") (pin "42") (pinfunction "PIO0_23/AD7_42") (pintype "bidirectional"))
    )
    (net (code "71") (name "VUSB") (class "Default")
      (node (ref "C10") (pin "1") (pinfunction "1_1") (pintype "passive"))
      (node (ref "IC4") (pin "19") (pinfunction "~{RESET}_19") (pintype "input"))
      (node (ref "IC4") (pin "20") (pinfunction "VCC_20") (pintype "power_in"))
      (node (ref "IC4") (pin "4") (pinfunction "VCCIO_4") (pintype "power_in"))
      (node (ref "RB2") (pin "2") (pinfunction "2_2") (pintype "passive"))
      (node (ref "RB6") (pin "2") (pinfunction "2_2") (pintype "passive"))
      (node (ref "USB1") (pin "P1") (pinfunction "VUSB_P1") (pintype "bidirectional"))
    )
    (net (code "72") (name "unconnected-(IC2-OUT-Pad4)") (class "Default")
      (node (ref "IC2") (pin "4") (pinfunction "OUT_4") (pintype "output"))
    )
    (net (code "73") (name "unconnected-(IC3A-EI-Pad11)") (class "Default")
      (node (ref "IC3") (pin "11") (pinfunction "EI_11") (pintype "input"))
    )
    (net (code "74") (name "unconnected-(IC3A-EO-Pad12)") (class "Default")
      (node (ref "IC3") (pin "12") (pinfunction "EO_12") (pintype "output"))
    )
    (net (code "75") (name "unconnected-(IC3A-FI-Pad14)") (class "Default")
      (node (ref "IC3") (pin "14") (pinfunction "FI_14") (pintype "input"))
    )
    (net (code "76") (name "unconnected-(IC3A-FO-Pad15)") (class "Default")
      (node (ref "IC3") (pin "15") (pinfunction "FO_15") (pintype "output"))
    )
    (net (code "77") (name "unconnected-(IC4-CBUS2-Pad13)") (class "Default")
      (node (ref "IC4") (pin "13") (pinfunction "CBUS2_13") (pintype "bidirectional"))
    )
    (net (code "78") (name "unconnected-(IC4-CBUS3-Pad14)") (class "Default")
      (node (ref "IC4") (pin "14") (pinfunction "CBUS3_14") (pintype "bidirectional"))
    )
    (net (code "79") (name "unconnected-(IC4-CBUS4-Pad12)") (class "Default")
      (node (ref "IC4") (pin "12") (pinfunction "CBUS4_12") (pintype "bidirectional"))
    )
    (net (code "80") (name "unconnected-(IC4-OSCI-Pad27)") (class "Default")
      (node (ref "IC4") (pin "27") (pinfunction "OSCI_27") (pintype "input"))
    )
    (net (code "81") (name "unconnected-(IC4-OSCO-Pad28)") (class "Default")
      (node (ref "IC4") (pin "28") (pinfunction "OSCO_28") (pintype "output"))
    )
    (net (code "82") (name "unconnected-(IC4-~{CTS}-Pad11)") (class "Default")
      (node (ref "IC4") (pin "11") (pinfunction "~{CTS}_11") (pintype "input"))
    )
    (net (code "83") (name "unconnected-(IC4-~{DCD}-Pad10)") (class "Default")
      (node (ref "IC4") (pin "10") (pinfunction "~{DCD}_10") (pintype "input"))
    )
    (net (code "84") (name "unconnected-(IC4-~{DSR}-Pad9)") (class "Default")
      (node (ref "IC4") (pin "9") (pinfunction "~{DSR}_9") (pintype "input"))
    )
    (net (code "85") (name "unconnected-(IC4-~{DTR}-Pad2)") (class "Default")
      (node (ref "IC4") (pin "2") (pinfunction "~{DTR}_2") (pintype "output"))
    )
    (net (code "86") (name "unconnected-(IC4-~{RI}-Pad6)") (class "Default")
      (node (ref "IC4") (pin "6") (pinfunction "~{RI}_6") (pintype "input"))
    )
    (net (code "87") (name "unconnected-(IC4-~{RTS}-Pad3)") (class "Default")
      (node (ref "IC4") (pin "3") (pinfunction "~{RTS}_3") (pintype "output"))
    )
    (net (code "88") (name "unconnected-(J1-GND-PadP$4)") (class "Default")
      (node (ref "J1") (pin "P$4") (pinfunction "GND_P$4") (pintype "bidirectional"))
    )
    (net (code "89") (name "unconnected-(J2-Pad4)") (class "Default")
      (node (ref "J2") (pin "4") (pinfunction "4_4") (pintype "passive"))
    )
    (net (code "90") (name "unconnected-(J2-Pad7)") (class "Default")
      (node (ref "J2") (pin "7") (pinfunction "7_7") (pintype "passive"))
    )
    (net (code "91") (name "unconnected-(J2-Pad8)") (class "Default")
      (node (ref "J2") (pin "8") (pinfunction "8_8") (pintype "passive"))
    )
    (net (code "92") (name "unconnected-(JP4-Pad1)") (class "Default")
      (node (ref "JP4") (pin "1") (pinfunction "1_1") (pintype "passive"))
    )
    (net (code "93") (name "unconnected-(JP4-Pad5)") (class "Default")
      (node (ref "JP4") (pin "5") (pinfunction "5_5") (pintype "passive"))
    )
    (net (code "94") (name "unconnected-(U$1-OSC-Pad3)") (class "Default")
      (node (ref "U$1") (pin "3") (pinfunction "OSC_3") (pintype "output"))
    )
    (net (code "95") (name "unconnected-(U$1-SD-Pad10)") (class "Default")
      (node (ref "U$1") (pin "10") (pinfunction "SD_10") (pintype "output"))
    )
    (net (code "96") (name "unconnected-(U$1-VREF-Pad16)") (class "Default")
      (node (ref "U$1") (pin "16") (pinfunction "VREF_16") (pintype "output"))
    )
    (net (code "97") (name "unconnected-(U1-NC-Pad1)") (class "Default")
      (node (ref "U1") (pin "1") (pinfunction "NC_1") (pintype "no_connect"))
    )
    (net (code "98") (name "unconnected-(U3-Pad3.3V)") (class "Default")
      (node (ref "U3") (pin "3.3V") (pinfunction "3.3V_3.3V") (pintype "bidirectional"))
    )
    (net (code "99") (name "unconnected-(U3-Pad5V)") (class "Default")
      (node (ref "U3") (pin "5V") (pinfunction "5V_5V") (pintype "bidirectional"))
    )
    (net (code "100") (name "unconnected-(U3-PadAREF)") (class "Default")
      (node (ref "U3") (pin "AREF") (pinfunction "AREF_AREF") (pintype "bidirectional"))
    )
    (net (code "101") (name "unconnected-(U3-PadRES)") (class "Default")
      (node (ref "U3") (pin "RES") (pinfunction "RES_RES") (pintype "bidirectional"))
    )
    (net (code "102") (name "unconnected-(U4-NC-Pad6)") (class "Default")
      (node (ref "U4") (pin "6") (pinfunction "NC_6") (pintype "no_connect"))
    )
    (net (code "103") (name "unconnected-(U4-NC_2-Pad5)") (class "Default")
      (node (ref "U4") (pin "5") (pinfunction "NC_2_5") (pintype "no_connect"))
    )
    (net (code "104") (name "unconnected-(U6-PIO0_2{slash}SSEL0{slash}CT16B0_CAP0-Pad10)") (class "Default")
      (node (ref "U6") (pin "10") (pinfunction "PIO0_2/SSEL0/CT16B0_CAP0_10") (pintype "bidirectional"))
    )
    (net (code "105") (name "unconnected-(U6-PIO0_8{slash}MISO0{slash}CT16B0_MAT0-Pad27)") (class "Default")
      (node (ref "U6") (pin "27") (pinfunction "PIO0_8/MISO0/CT16B0_MAT0_27") (pintype "bidirectional"))
    )
    (net (code "106") (name "unconnected-(U6-PIO0_9{slash}MOSI0{slash}CT16B0_MAT1-Pad28)") (class "Default")
      (node (ref "U6") (pin "28") (pinfunction "PIO0_9/MOSI0/CT16B0_MAT1_28") (pintype "bidirectional"))
    )
    (net (code "107") (name "unconnected-(U6-PIO0_17{slash}~{RTS}{slash}CT32B0_CAP0{slash}SCLK-Pad45)") (class "Default")
      (node (ref "U6") (pin "45") (pinfunction "PIO0_17/~{RTS}/CT32B0_CAP0/SCLK_45") (pintype "bidirectional"))
    )
    (net (code "108") (name "unconnected-(U6-PIO0_20{slash}CT16B1_CAP0-Pad9)") (class "Default")
      (node (ref "U6") (pin "9") (pinfunction "PIO0_20/CT16B1_CAP0_9") (pintype "bidirectional"))
    )
    (net (code "109") (name "unconnected-(U6-PIO0_22{slash}AD6{slash}CT16B1_MAT1{slash}MISO1-Pad30)") (class "Default")
      (node (ref "U6") (pin "30") (pinfunction "PIO0_22/AD6/CT16B1_MAT1/MISO1_30") (pintype "bidirectional"))
    )
    (net (code "110") (name "unconnected-(U6-PIO1_16{slash}~{RI}{slash}CT16B0_CAP0-Pad48)") (class "Default")
      (node (ref "U6") (pin "48") (pinfunction "PIO1_16/~{RI}/CT16B0_CAP0_48") (pintype "bidirectional"))
    )
    (net (code "111") (name "unconnected-(U6-PIO1_20{slash}~{DSR}{slash}SCK1-Pad13)") (class "Default")
      (node (ref "U6") (pin "13") (pinfunction "PIO1_20/~{DSR}/SCK1_13") (pintype "bidirectional"))
    )
    (net (code "112") (name "unconnected-(U6-PIO1_21{slash}~{DCD}{slash}MISO1-Pad26)") (class "Default")
      (node (ref "U6") (pin "26") (pinfunction "PIO1_21/~{DCD}/MISO1_26") (pintype "bidirectional"))
    )
    (net (code "113") (name "unconnected-(U6-PIO1_27{slash}CT32B0_MAT3{slash}TXD-Pad12)") (class "Default")
      (node (ref "U6") (pin "12") (pinfunction "PIO1_27/CT32B0_MAT3/TXD_12") (pintype "bidirectional"))
    )
    (net (code "114") (name "unconnected-(U6-PIO1_29{slash}SCK0{slash}CT32B0_CAP1-Pad31)") (class "Default")
      (node (ref "U6") (pin "31") (pinfunction "PIO1_29/SCK0/CT32B0_CAP1_31") (pintype "bidirectional"))
    )
    (net (code "115") (name "unconnected-(U6-USB_DM-Pad19)") (class "Default")
      (node (ref "U6") (pin "19") (pinfunction "USB_DM_19") (pintype "passive"))
    )
    (net (code "116") (name "unconnected-(U6-USB_DP-Pad20)") (class "Default")
      (node (ref "U6") (pin "20") (pinfunction "USB_DP_20") (pintype "passive"))
    )
    (net (code "117") (name "unconnected-(USB1A-BODY-PadBODY@1)") (class "Default")
      (node (ref "USB1") (pin "BODY@1") (pinfunction "BODY_BODY@1") (pintype "tri_state"))
    )
    (net (code "118") (name "unconnected-(USB1A-BODY-PadBODY@2)") (class "Default")
      (node (ref "USB1") (pin "BODY@2") (pinfunction "BODY_BODY@2") (pintype "tri_state"))
    )
    (net (code "119") (name "unconnected-(USB1A-BODY-PadBODY@3)") (class "Default")
      (node (ref "USB1") (pin "BODY@3") (pinfunction "BODY_BODY@3") (pintype "tri_state"))
    )
    (net (code "120") (name "unconnected-(USB1A-BODY-PadBODY@4)") (class "Default")
      (node (ref "USB1") (pin "BODY@4") (pinfunction "BODY_BODY@4") (pintype "tri_state"))
    )
    (net (code "121") (name "unconnected-(USB1B-USBID-PadP4)") (class "Default")
      (node (ref "USB1") (pin "P4") (pinfunction "USBID_P4") (pintype "bidirectional"))
    )
    (net (code "122") (name "~{RESET}") (class "Default")
      (node (ref "C14") (pin "1") (pinfunction "1_1") (pintype "passive"))
      (node (ref "J2") (pin "6") (pinfunction "6_6") (pintype "passive"))
      (node (ref "RB3") (pin "2") (pinfunction "2_2") (pintype "passive"))
      (node (ref "U6") (pin "3") (pinfunction "~{RESET}/PIO0_0_3") (pintype "passive"))
    )
  )
)
